# KF01A-D.net
KiCad netlist of a schematic drawn in Altium Designer
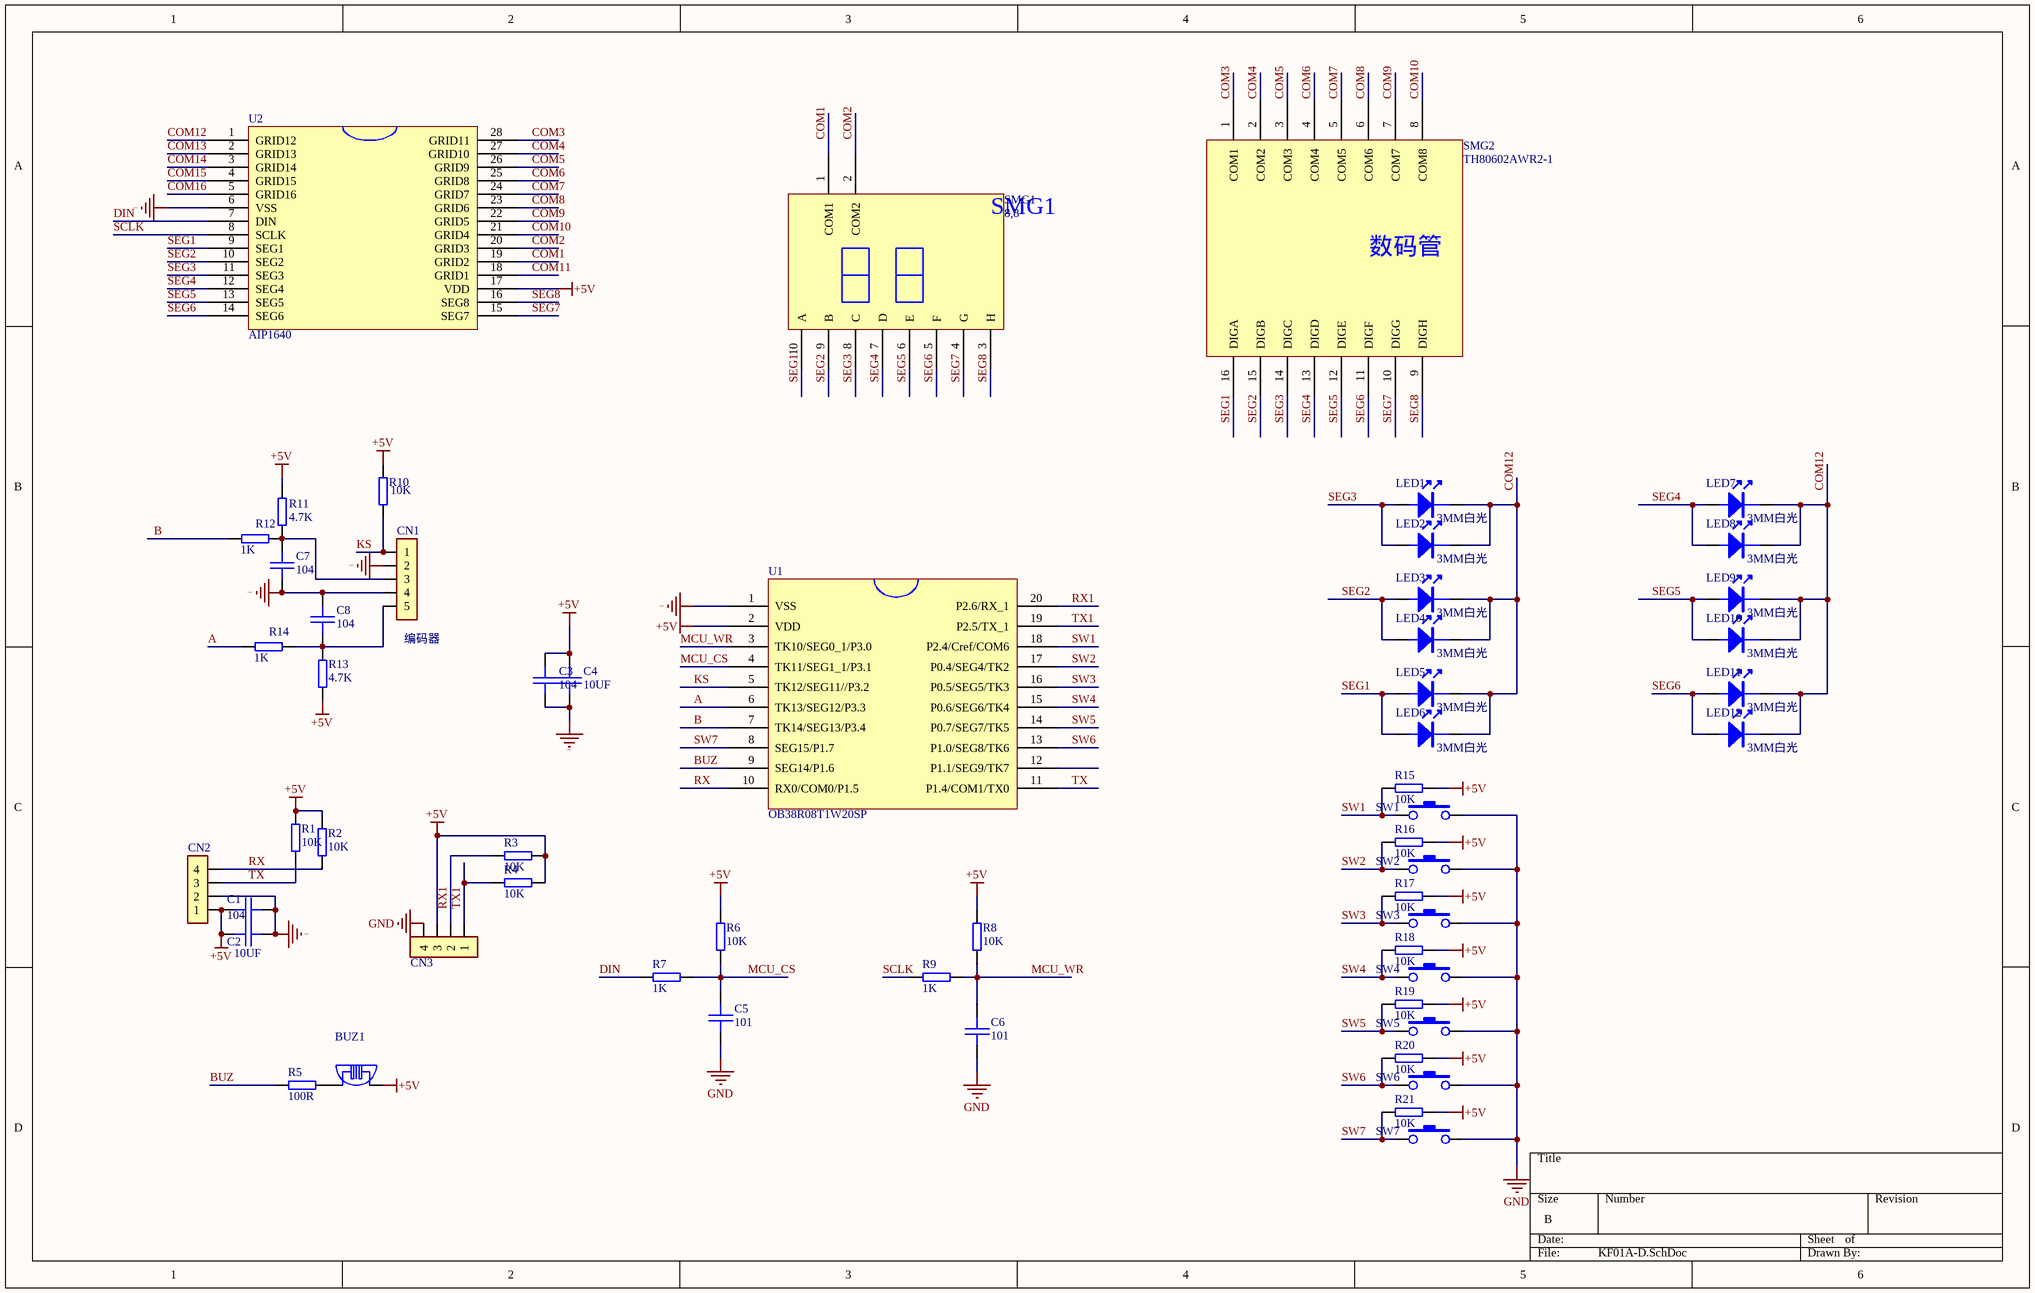
[diagram p0: KF01A-D.SchDoc]

(export (version "E")
  (design (tool "Eeschema 10.0.6"))
  (components
    (comp (ref "BUZ1")
      (value "~")
      (footprint "MD-PCB-201802标准化:BUZ-7.5-15-AI")
      (description "BUZ")
      (libsource (lib "Md-SCH-201802标准化.LIB") (part "BUZ"))
    )
    (comp (ref "C1")
      (value "104")
      (footprint "c0805")
      (description "CAP")
      (libsource (lib "Md-SCH-201802标准化.LIB") (part "C"))
    )
    (comp (ref "C2")
      (value "10UF")
      (footprint "c1206")
      (description "CAP")
      (libsource (lib "Md-SCH-201802标准化.LIB") (part "C"))
    )
    (comp (ref "C3")
      (value "104")
      (footprint "c0805")
      (description "CAP")
      (libsource (lib "Md-SCH-201802标准化.LIB") (part "C"))
    )
    (comp (ref "C4")
      (value "10UF")
      (footprint "c1206")
      (description "CAP")
      (libsource (lib "Md-SCH-201802标准化.LIB") (part "C"))
    )
    (comp (ref "C5")
      (value "101")
      (footprint "c0805")
      (description "CAP")
      (libsource (lib "Md-SCH-201802标准化.LIB") (part "C"))
    )
    (comp (ref "C6")
      (value "101")
      (footprint "c0805")
      (description "CAP")
      (libsource (lib "Md-SCH-201802标准化.LIB") (part "C"))
    )
    (comp (ref "C7")
      (value "104")
      (footprint "c0805")
      (description "CAP")
      (libsource (lib "Md-SCH-201802标准化.LIB") (part "C"))
    )
    (comp (ref "C8")
      (value "104")
      (footprint "c0805")
      (description "CAP")
      (libsource (lib "Md-SCH-201802标准化.LIB") (part "C"))
    )
    (comp (ref "CN1")
      (value "编码器")
      (footprint "抄板封装:编码器")
      (description "CN5")
      (libsource (lib "Md-SCH-201802标准化.LIB") (part "CN5"))
    )
    (comp (ref "CN2")
      (value "~")
      (footprint "CN-2.54-4-X")
      (description "CN4")
      (libsource (lib "Md-SCH-201802标准化.LIB") (part "CN4"))
    )
    (comp (ref "CN3")
      (value "~")
      (footprint "CN-2.54-4-P")
      (description "CN4")
      (libsource (lib "") (part "CN4_1"))
    )
    (comp (ref "LED1")
      (value "3MM白光")
      (footprint "通用库 MD-PCB-20181218:led3")
      (description "LED")
      (libsource (lib "Md-SCH-201802标准化.LIB") (part "DL"))
    )
    (comp (ref "LED2")
      (value "3MM白光")
      (footprint "通用库 MD-PCB-20181218:led3")
      (description "LED")
      (libsource (lib "Md-SCH-201802标准化.LIB") (part "DL"))
    )
    (comp (ref "LED3")
      (value "3MM白光")
      (footprint "通用库 MD-PCB-20181218:led3")
      (description "LED")
      (libsource (lib "Md-SCH-201802标准化.LIB") (part "DL"))
    )
    (comp (ref "LED4")
      (value "3MM白光")
      (footprint "通用库 MD-PCB-20181218:led3")
      (description "LED")
      (libsource (lib "Md-SCH-201802标准化.LIB") (part "DL"))
    )
    (comp (ref "LED5")
      (value "3MM白光")
      (footprint "通用库 MD-PCB-20181218:led3")
      (description "LED")
      (libsource (lib "Md-SCH-201802标准化.LIB") (part "DL"))
    )
    (comp (ref "LED6")
      (value "3MM白光")
      (footprint "通用库 MD-PCB-20181218:led3")
      (description "LED")
      (libsource (lib "Md-SCH-201802标准化.LIB") (part "DL"))
    )
    (comp (ref "LED7")
      (value "3MM白光")
      (footprint "通用库 MD-PCB-20181218:led3")
      (description "LED")
      (libsource (lib "Md-SCH-201802标准化.LIB") (part "DL"))
    )
    (comp (ref "LED8")
      (value "3MM白光")
      (footprint "通用库 MD-PCB-20181218:led3")
      (description "LED")
      (libsource (lib "Md-SCH-201802标准化.LIB") (part "DL"))
    )
    (comp (ref "LED9")
      (value "3MM白光")
      (footprint "通用库 MD-PCB-20181218:led3")
      (description "LED")
      (libsource (lib "Md-SCH-201802标准化.LIB") (part "DL"))
    )
    (comp (ref "LED10")
      (value "3MM白光")
      (footprint "通用库 MD-PCB-20181218:led3")
      (description "LED")
      (libsource (lib "Md-SCH-201802标准化.LIB") (part "DL"))
    )
    (comp (ref "LED11")
      (value "3MM白光")
      (footprint "通用库 MD-PCB-20181218:led3")
      (description "LED")
      (libsource (lib "Md-SCH-201802标准化.LIB") (part "DL"))
    )
    (comp (ref "LED12")
      (value "3MM白光")
      (footprint "通用库 MD-PCB-20181218:led3")
      (description "LED")
      (libsource (lib "Md-SCH-201802标准化.LIB") (part "DL"))
    )
    (comp (ref "R1")
      (value "10K")
      (footprint "R0805")
      (description "RES")
      (libsource (lib "Md-SCH-201802标准化.LIB") (part "R"))
    )
    (comp (ref "R2")
      (value "10K")
      (footprint "R0805")
      (description "RES")
      (libsource (lib "Md-SCH-201802标准化.LIB") (part "R"))
    )
    (comp (ref "R3")
      (value "10K")
      (footprint "R0805")
      (description "RES")
      (libsource (lib "Md-SCH-201802标准化.LIB") (part "R"))
    )
    (comp (ref "R4")
      (value "10K")
      (footprint "R0805")
      (description "RES")
      (libsource (lib "Md-SCH-201802标准化.LIB") (part "R"))
    )
    (comp (ref "R5")
      (value "100R")
      (footprint "R0805")
      (description "RES")
      (libsource (lib "Md-SCH-201802标准化.LIB") (part "R"))
    )
    (comp (ref "R6")
      (value "10K")
      (footprint "R0805")
      (description "RES")
      (libsource (lib "Md-SCH-201802标准化.LIB") (part "R"))
    )
    (comp (ref "R7")
      (value "1K")
      (footprint "R0805")
      (description "RES")
      (libsource (lib "Md-SCH-201802标准化.LIB") (part "R"))
    )
    (comp (ref "R8")
      (value "10K")
      (footprint "R0805")
      (description "RES")
      (libsource (lib "Md-SCH-201802标准化.LIB") (part "R"))
    )
    (comp (ref "R9")
      (value "1K")
      (footprint "R0805")
      (description "RES")
      (libsource (lib "Md-SCH-201802标准化.LIB") (part "R"))
    )
    (comp (ref "R10")
      (value "10K")
      (footprint "R0805")
      (description "RES")
      (libsource (lib "Md-SCH-201802标准化.LIB") (part "R"))
    )
    (comp (ref "R11")
      (value "4.7K")
      (footprint "R0805")
      (description "RES")
      (libsource (lib "Md-SCH-201802标准化.LIB") (part "R"))
    )
    (comp (ref "R12")
      (value "1K")
      (footprint "R0805")
      (description "RES")
      (libsource (lib "Md-SCH-201802标准化.LIB") (part "R"))
    )
    (comp (ref "R13")
      (value "4.7K")
      (footprint "R0805")
      (description "RES")
      (libsource (lib "Md-SCH-201802标准化.LIB") (part "R"))
    )
    (comp (ref "R14")
      (value "1K")
      (footprint "R0805")
      (description "RES")
      (libsource (lib "Md-SCH-201802标准化.LIB") (part "R"))
    )
    (comp (ref "R15")
      (value "10K")
      (footprint "R0805")
      (description "RES")
      (libsource (lib "Md-SCH-201802标准化.LIB") (part "R"))
    )
    (comp (ref "R16")
      (value "10K")
      (footprint "R0805")
      (description "RES")
      (libsource (lib "Md-SCH-201802标准化.LIB") (part "R"))
    )
    (comp (ref "R17")
      (value "10K")
      (footprint "R0805")
      (description "RES")
      (libsource (lib "Md-SCH-201802标准化.LIB") (part "R"))
    )
    (comp (ref "R18")
      (value "10K")
      (footprint "R0805")
      (description "RES")
      (libsource (lib "Md-SCH-201802标准化.LIB") (part "R"))
    )
    (comp (ref "R19")
      (value "10K")
      (footprint "R0805")
      (description "RES")
      (libsource (lib "Md-SCH-201802标准化.LIB") (part "R"))
    )
    (comp (ref "R20")
      (value "10K")
      (footprint "R0805")
      (description "RES")
      (libsource (lib "Md-SCH-201802标准化.LIB") (part "R"))
    )
    (comp (ref "R21")
      (value "10K")
      (footprint "R0805")
      (description "RES")
      (libsource (lib "Md-SCH-201802标准化.LIB") (part "R"))
    )
    (comp (ref "SMG1") (value "8,8") (footprint "TH34251AW1-1") (libsource (lib "CS1621G0") (part "8,8")))
    (comp (ref "SMG2")
      (value "TH80602AWR2-1")
      (footprint "TH80602AWR2-1")
      (libsource (lib "CS1621G0") (part "TH80602AWR2-1"))
    )
    (comp (ref "SW1")
      (value "~")
      (footprint "KEY-4/4")
      (description "KEY")
      (libsource (lib "Md-SCH-201802标准化.LIB") (part "KQ"))
    )
    (comp (ref "SW2")
      (value "~")
      (footprint "KEY-4/4")
      (description "KEY")
      (libsource (lib "Md-SCH-201802标准化.LIB") (part "KQ"))
    )
    (comp (ref "SW3")
      (value "~")
      (footprint "KEY-4/4")
      (description "KEY")
      (libsource (lib "Md-SCH-201802标准化.LIB") (part "KQ"))
    )
    (comp (ref "SW4")
      (value "~")
      (footprint "KEY-4/4")
      (description "KEY")
      (libsource (lib "Md-SCH-201802标准化.LIB") (part "KQ"))
    )
    (comp (ref "SW5")
      (value "~")
      (footprint "KEY-4/4")
      (description "KEY")
      (libsource (lib "Md-SCH-201802标准化.LIB") (part "KQ"))
    )
    (comp (ref "SW6")
      (value "~")
      (footprint "KEY-4/4")
      (description "KEY")
      (libsource (lib "Md-SCH-201802标准化.LIB") (part "KQ"))
    )
    (comp (ref "SW7")
      (value "~")
      (footprint "KEY-4/4")
      (description "KEY")
      (libsource (lib "Md-SCH-201802标准化.LIB") (part "KQ"))
    )
    (comp (ref "U1")
      (value "OB38R08T1W20SP")
      (footprint "通用库 MD-PCB-20181218:SOP20")
      (libsource (lib "Md-SCH-201802标准化.LIB") (part "IC-20"))
    )
    (comp (ref "U2")
      (value "AIP1640")
      (footprint "通用库 MD-PCB-20181218:SOP28")
      (libsource (lib "*") (part "TM1628"))
    )
  )
  (nets
    (net (code "1") (name "+5V") (class "Default")
      (node (ref "BUZ1") (pin "2") (pinfunction "2_2") (pintype "passive"))
      (node (ref "C1") (pin "2") (pinfunction "2_2") (pintype "passive"))
      (node (ref "C2") (pin "2") (pinfunction "2_2") (pintype "passive"))
      (node (ref "C3") (pin "1") (pinfunction "1_1") (pintype "passive"))
      (node (ref "C4") (pin "1") (pinfunction "1_1") (pintype "passive"))
      (node (ref "CN2") (pin "1") (pinfunction "1_1") (pintype "passive"))
      (node (ref "CN3") (pin "3") (pinfunction "3_3") (pintype "passive"))
      (node (ref "R1") (pin "2") (pinfunction "2_2") (pintype "passive"))
      (node (ref "R10") (pin "2") (pinfunction "2_2") (pintype "passive"))
      (node (ref "R11") (pin "1") (pinfunction "1_1") (pintype "passive"))
      (node (ref "R13") (pin "2") (pinfunction "2_2") (pintype "passive"))
      (node (ref "R15") (pin "1") (pinfunction "1_1") (pintype "passive"))
      (node (ref "R16") (pin "1") (pinfunction "1_1") (pintype "passive"))
      (node (ref "R17") (pin "1") (pinfunction "1_1") (pintype "passive"))
      (node (ref "R18") (pin "1") (pinfunction "1_1") (pintype "passive"))
      (node (ref "R19") (pin "1") (pinfunction "1_1") (pintype "passive"))
      (node (ref "R2") (pin "2") (pinfunction "2_2") (pintype "passive"))
      (node (ref "R20") (pin "1") (pinfunction "1_1") (pintype "passive"))
      (node (ref "R21") (pin "1") (pinfunction "1_1") (pintype "passive"))
      (node (ref "R3") (pin "1") (pinfunction "1_1") (pintype "passive"))
      (node (ref "R4") (pin "1") (pinfunction "1_1") (pintype "passive"))
      (node (ref "R6") (pin "2") (pinfunction "2_2") (pintype "passive"))
      (node (ref "R8") (pin "2") (pinfunction "2_2") (pintype "passive"))
      (node (ref "U1") (pin "2") (pinfunction "VDD_2") (pintype "passive"))
      (node (ref "U2") (pin "17") (pinfunction "VDD_17") (pintype "passive"))
    )
    (net (code "2") (name "/A") (class "Default")
      (node (ref "R14") (pin "1") (pinfunction "1_1") (pintype "passive"))
      (node (ref "U1") (pin "6") (pinfunction "TK13/SEG12/P3.3_6") (pintype "passive"))
    )
    (net (code "3") (name "/B") (class "Default")
      (node (ref "R12") (pin "1") (pinfunction "1_1") (pintype "passive"))
      (node (ref "U1") (pin "7") (pinfunction "TK14/SEG13/P3.4_7") (pintype "passive"))
    )
    (net (code "4") (name "/BUZ") (class "Default")
      (node (ref "R5") (pin "2") (pinfunction "2_2") (pintype "passive"))
      (node (ref "U1") (pin "9") (pinfunction "SEG14/P1.6_9") (pintype "passive"))
    )
    (net (code "5") (name "/COM1") (class "Default")
      (node (ref "SMG1") (pin "1") (pinfunction "COM1_1") (pintype "passive"))
      (node (ref "U2") (pin "19") (pinfunction "GRID2_19") (pintype "passive"))
    )
    (net (code "6") (name "/COM2") (class "Default")
      (node (ref "SMG1") (pin "2") (pinfunction "COM2_2") (pintype "passive"))
      (node (ref "U2") (pin "20") (pinfunction "GRID3_20") (pintype "passive"))
    )
    (net (code "7") (name "/COM3") (class "Default")
      (node (ref "SMG2") (pin "1") (pinfunction "COM1_1") (pintype "passive"))
      (node (ref "U2") (pin "28") (pinfunction "GRID11_28") (pintype "passive"))
    )
    (net (code "8") (name "/COM4") (class "Default")
      (node (ref "SMG2") (pin "2") (pinfunction "COM2_2") (pintype "passive"))
      (node (ref "U2") (pin "27") (pinfunction "GRID10_27") (pintype "passive"))
    )
    (net (code "9") (name "/COM5") (class "Default")
      (node (ref "SMG2") (pin "3") (pinfunction "COM3_3") (pintype "passive"))
      (node (ref "U2") (pin "26") (pinfunction "GRID9_26") (pintype "passive"))
    )
    (net (code "10") (name "/COM6") (class "Default")
      (node (ref "SMG2") (pin "4") (pinfunction "COM4_4") (pintype "passive"))
      (node (ref "U2") (pin "25") (pinfunction "GRID8_25") (pintype "passive"))
    )
    (net (code "11") (name "/COM7") (class "Default")
      (node (ref "SMG2") (pin "5") (pinfunction "COM5_5") (pintype "passive"))
      (node (ref "U2") (pin "24") (pinfunction "GRID7_24") (pintype "passive"))
    )
    (net (code "12") (name "/COM8") (class "Default")
      (node (ref "SMG2") (pin "6") (pinfunction "COM6_6") (pintype "passive"))
      (node (ref "U2") (pin "23") (pinfunction "GRID6_23") (pintype "passive"))
    )
    (net (code "13") (name "/COM9") (class "Default")
      (node (ref "SMG2") (pin "7") (pinfunction "COM7_7") (pintype "passive"))
      (node (ref "U2") (pin "22") (pinfunction "GRID5_22") (pintype "passive"))
    )
    (net (code "14") (name "/COM10") (class "Default")
      (node (ref "SMG2") (pin "8") (pinfunction "COM8_8") (pintype "passive"))
      (node (ref "U2") (pin "21") (pinfunction "GRID4_21") (pintype "passive"))
    )
    (net (code "15") (name "/COM11") (class "Default")
      (node (ref "U2") (pin "18") (pinfunction "GRID1_18") (pintype "passive"))
    )
    (net (code "16") (name "/COM12") (class "Default")
      (node (ref "LED1") (pin "K") (pinfunction "K_K") (pintype "passive"))
      (node (ref "LED10") (pin "K") (pinfunction "K_K") (pintype "passive"))
      (node (ref "LED11") (pin "K") (pinfunction "K_K") (pintype "passive"))
      (node (ref "LED12") (pin "K") (pinfunction "K_K") (pintype "passive"))
      (node (ref "LED2") (pin "K") (pinfunction "K_K") (pintype "passive"))
      (node (ref "LED3") (pin "K") (pinfunction "K_K") (pintype "passive"))
      (node (ref "LED4") (pin "K") (pinfunction "K_K") (pintype "passive"))
      (node (ref "LED5") (pin "K") (pinfunction "K_K") (pintype "passive"))
      (node (ref "LED6") (pin "K") (pinfunction "K_K") (pintype "passive"))
      (node (ref "LED7") (pin "K") (pinfunction "K_K") (pintype "passive"))
      (node (ref "LED8") (pin "K") (pinfunction "K_K") (pintype "passive"))
      (node (ref "LED9") (pin "K") (pinfunction "K_K") (pintype "passive"))
      (node (ref "U2") (pin "1") (pinfunction "GRID12_1") (pintype "passive"))
    )
    (net (code "17") (name "/COM13") (class "Default")
      (node (ref "U2") (pin "2") (pinfunction "GRID13_2") (pintype "passive"))
    )
    (net (code "18") (name "/COM14") (class "Default")
      (node (ref "U2") (pin "3") (pinfunction "GRID14_3") (pintype "passive"))
    )
    (net (code "19") (name "/COM15") (class "Default")
      (node (ref "U2") (pin "4") (pinfunction "GRID15_4") (pintype "passive"))
    )
    (net (code "20") (name "/COM16") (class "Default")
      (node (ref "U2") (pin "5") (pinfunction "GRID16_5") (pintype "passive"))
    )
    (net (code "21") (name "/DIN") (class "Default")
      (node (ref "R7") (pin "2") (pinfunction "2_2") (pintype "passive"))
      (node (ref "U2") (pin "7") (pinfunction "DIN_7") (pintype "passive"))
    )
    (net (code "22") (name "/KS") (class "Default")
      (node (ref "CN1") (pin "1") (pinfunction "1_1") (pintype "passive"))
      (node (ref "R10") (pin "1") (pinfunction "1_1") (pintype "passive"))
      (node (ref "U1") (pin "5") (pinfunction "TK12/SEG11//P3.2_5") (pintype "passive"))
    )
    (net (code "23") (name "/MCU_CS") (class "Default")
      (node (ref "C5") (pin "1") (pinfunction "1_1") (pintype "passive"))
      (node (ref "R6") (pin "1") (pinfunction "1_1") (pintype "passive"))
      (node (ref "R7") (pin "1") (pinfunction "1_1") (pintype "passive"))
      (node (ref "U1") (pin "4") (pinfunction "TK11/SEG1_1/P3.1_4") (pintype "passive"))
    )
    (net (code "24") (name "/MCU_WR") (class "Default")
      (node (ref "C6") (pin "1") (pinfunction "1_1") (pintype "passive"))
      (node (ref "R8") (pin "1") (pinfunction "1_1") (pintype "passive"))
      (node (ref "R9") (pin "1") (pinfunction "1_1") (pintype "passive"))
      (node (ref "U1") (pin "3") (pinfunction "TK10/SEG0_1/P3.0_3") (pintype "passive"))
    )
    (net (code "25") (name "/RX") (class "Default")
      (node (ref "CN2") (pin "4") (pinfunction "4_4") (pintype "passive"))
      (node (ref "R2") (pin "1") (pinfunction "1_1") (pintype "passive"))
      (node (ref "U1") (pin "10") (pinfunction "RX0/COM0/P1.5_10") (pintype "passive"))
    )
    (net (code "26") (name "/RX1") (class "Default")
      (node (ref "CN3") (pin "2") (pinfunction "2_2") (pintype "passive"))
      (node (ref "R3") (pin "2") (pinfunction "2_2") (pintype "passive"))
      (node (ref "U1") (pin "20") (pinfunction "P2.6/RX_1_20") (pintype "passive"))
    )
    (net (code "27") (name "/SCLK") (class "Default")
      (node (ref "R9") (pin "2") (pinfunction "2_2") (pintype "passive"))
      (node (ref "U2") (pin "8") (pinfunction "SCLK_8") (pintype "passive"))
    )
    (net (code "28") (name "/SEG1") (class "Default")
      (node (ref "LED5") (pin "A") (pinfunction "A_A") (pintype "passive"))
      (node (ref "LED6") (pin "A") (pinfunction "A_A") (pintype "passive"))
      (node (ref "SMG1") (pin "10") (pinfunction "A_10") (pintype "passive"))
      (node (ref "SMG2") (pin "16") (pinfunction "DIGA_16") (pintype "passive"))
      (node (ref "U2") (pin "9") (pinfunction "SEG1_9") (pintype "passive"))
    )
    (net (code "29") (name "/SEG2") (class "Default")
      (node (ref "LED3") (pin "A") (pinfunction "A_A") (pintype "passive"))
      (node (ref "LED4") (pin "A") (pinfunction "A_A") (pintype "passive"))
      (node (ref "SMG1") (pin "9") (pinfunction "B_9") (pintype "passive"))
      (node (ref "SMG2") (pin "15") (pinfunction "DIGB_15") (pintype "passive"))
      (node (ref "U2") (pin "10") (pinfunction "SEG2_10") (pintype "passive"))
    )
    (net (code "30") (name "/SEG3") (class "Default")
      (node (ref "LED1") (pin "A") (pinfunction "A_A") (pintype "passive"))
      (node (ref "LED2") (pin "A") (pinfunction "A_A") (pintype "passive"))
      (node (ref "SMG1") (pin "8") (pinfunction "C_8") (pintype "passive"))
      (node (ref "SMG2") (pin "14") (pinfunction "DIGC_14") (pintype "passive"))
      (node (ref "U2") (pin "11") (pinfunction "SEG3_11") (pintype "passive"))
    )
    (net (code "31") (name "/SEG4") (class "Default")
      (node (ref "LED7") (pin "A") (pinfunction "A_A") (pintype "passive"))
      (node (ref "LED8") (pin "A") (pinfunction "A_A") (pintype "passive"))
      (node (ref "SMG1") (pin "7") (pinfunction "D_7") (pintype "passive"))
      (node (ref "SMG2") (pin "13") (pinfunction "DIGD_13") (pintype "passive"))
      (node (ref "U2") (pin "12") (pinfunction "SEG4_12") (pintype "passive"))
    )
    (net (code "32") (name "/SEG5") (class "Default")
      (node (ref "LED10") (pin "A") (pinfunction "A_A") (pintype "passive"))
      (node (ref "LED9") (pin "A") (pinfunction "A_A") (pintype "passive"))
      (node (ref "SMG1") (pin "6") (pinfunction "E_6") (pintype "passive"))
      (node (ref "SMG2") (pin "12") (pinfunction "DIGE_12") (pintype "passive"))
      (node (ref "U2") (pin "13") (pinfunction "SEG5_13") (pintype "passive"))
    )
    (net (code "33") (name "/SEG6") (class "Default")
      (node (ref "LED11") (pin "A") (pinfunction "A_A") (pintype "passive"))
      (node (ref "LED12") (pin "A") (pinfunction "A_A") (pintype "passive"))
      (node (ref "SMG1") (pin "5") (pinfunction "F_5") (pintype "passive"))
      (node (ref "SMG2") (pin "11") (pinfunction "DIGF_11") (pintype "passive"))
      (node (ref "U2") (pin "14") (pinfunction "SEG6_14") (pintype "passive"))
    )
    (net (code "34") (name "/SEG7") (class "Default")
      (node (ref "SMG1") (pin "4") (pinfunction "G_4") (pintype "passive"))
      (node (ref "SMG2") (pin "10") (pinfunction "DIGG_10") (pintype "passive"))
      (node (ref "U2") (pin "15") (pinfunction "SEG7_15") (pintype "passive"))
    )
    (net (code "35") (name "/SEG8") (class "Default")
      (node (ref "SMG1") (pin "3") (pinfunction "H_3") (pintype "passive"))
      (node (ref "SMG2") (pin "9") (pinfunction "DIGH_9") (pintype "passive"))
      (node (ref "U2") (pin "16") (pinfunction "SEG8_16") (pintype "passive"))
    )
    (net (code "36") (name "/SW1") (class "Default")
      (node (ref "R15") (pin "2") (pinfunction "2_2") (pintype "passive"))
      (node (ref "SW1") (pin "1") (pinfunction "1_1") (pintype "passive"))
      (node (ref "U1") (pin "18") (pinfunction "P2.4/Cref/COM6_18") (pintype "passive"))
    )
    (net (code "37") (name "/SW2") (class "Default")
      (node (ref "R16") (pin "2") (pinfunction "2_2") (pintype "passive"))
      (node (ref "SW2") (pin "1") (pinfunction "1_1") (pintype "passive"))
      (node (ref "U1") (pin "17") (pinfunction "P0.4/SEG4/TK2_17") (pintype "passive"))
    )
    (net (code "38") (name "/SW3") (class "Default")
      (node (ref "R17") (pin "2") (pinfunction "2_2") (pintype "passive"))
      (node (ref "SW3") (pin "1") (pinfunction "1_1") (pintype "passive"))
      (node (ref "U1") (pin "16") (pinfunction "P0.5/SEG5/TK3_16") (pintype "passive"))
    )
    (net (code "39") (name "/SW4") (class "Default")
      (node (ref "R18") (pin "2") (pinfunction "2_2") (pintype "passive"))
      (node (ref "SW4") (pin "1") (pinfunction "1_1") (pintype "passive"))
      (node (ref "U1") (pin "15") (pinfunction "P0.6/SEG6/TK4_15") (pintype "passive"))
    )
    (net (code "40") (name "/SW5") (class "Default")
      (node (ref "R19") (pin "2") (pinfunction "2_2") (pintype "passive"))
      (node (ref "SW5") (pin "1") (pinfunction "1_1") (pintype "passive"))
      (node (ref "U1") (pin "14") (pinfunction "P0.7/SEG7/TK5_14") (pintype "passive"))
    )
    (net (code "41") (name "/SW6") (class "Default")
      (node (ref "R20") (pin "2") (pinfunction "2_2") (pintype "passive"))
      (node (ref "SW6") (pin "1") (pinfunction "1_1") (pintype "passive"))
      (node (ref "U1") (pin "13") (pinfunction "P1.0/SEG8/TK6_13") (pintype "passive"))
    )
    (net (code "42") (name "/SW7") (class "Default")
      (node (ref "R21") (pin "2") (pinfunction "2_2") (pintype "passive"))
      (node (ref "SW7") (pin "1") (pinfunction "1_1") (pintype "passive"))
      (node (ref "U1") (pin "8") (pinfunction "SEG15/P1.7_8") (pintype "passive"))
    )
    (net (code "43") (name "/TX") (class "Default")
      (node (ref "CN2") (pin "3") (pinfunction "3_3") (pintype "passive"))
      (node (ref "R1") (pin "1") (pinfunction "1_1") (pintype "passive"))
      (node (ref "U1") (pin "11") (pinfunction "P1.4/COM1/TX0_11") (pintype "passive"))
    )
    (net (code "44") (name "/TX1") (class "Default")
      (node (ref "CN3") (pin "1") (pinfunction "1_1") (pintype "passive"))
      (node (ref "R4") (pin "2") (pinfunction "2_2") (pintype "passive"))
      (node (ref "U1") (pin "19") (pinfunction "P2.5/TX_1_19") (pintype "passive"))
    )
    (net (code "45") (name "GND") (class "Default")
      (node (ref "C1") (pin "1") (pinfunction "1_1") (pintype "passive"))
      (node (ref "C2") (pin "1") (pinfunction "1_1") (pintype "passive"))
      (node (ref "C3") (pin "2") (pinfunction "2_2") (pintype "passive"))
      (node (ref "C4") (pin "2") (pinfunction "2_2") (pintype "passive"))
      (node (ref "C5") (pin "2") (pinfunction "2_2") (pintype "passive"))
      (node (ref "C6") (pin "2") (pinfunction "2_2") (pintype "passive"))
      (node (ref "C7") (pin "2") (pinfunction "2_2") (pintype "passive"))
      (node (ref "C8") (pin "1") (pinfunction "1_1") (pintype "passive"))
      (node (ref "CN1") (pin "2") (pinfunction "2_2") (pintype "passive"))
      (node (ref "CN1") (pin "4") (pinfunction "4_4") (pintype "passive"))
      (node (ref "CN2") (pin "2") (pinfunction "2_2") (pintype "passive"))
      (node (ref "CN3") (pin "4") (pinfunction "4_4") (pintype "passive"))
      (node (ref "SW1") (pin "2") (pinfunction "2_2") (pintype "passive"))
      (node (ref "SW2") (pin "2") (pinfunction "2_2") (pintype "passive"))
      (node (ref "SW3") (pin "2") (pinfunction "2_2") (pintype "passive"))
      (node (ref "SW4") (pin "2") (pinfunction "2_2") (pintype "passive"))
      (node (ref "SW5") (pin "2") (pinfunction "2_2") (pintype "passive"))
      (node (ref "SW6") (pin "2") (pinfunction "2_2") (pintype "passive"))
      (node (ref "SW7") (pin "2") (pinfunction "2_2") (pintype "passive"))
      (node (ref "U1") (pin "1") (pinfunction "VSS_1") (pintype "passive"))
      (node (ref "U2") (pin "6") (pinfunction "VSS_6") (pintype "passive"))
    )
    (net (code "46") (name "Net-(BUZ1-Pad1)") (class "Default")
      (node (ref "BUZ1") (pin "1") (pinfunction "1_1") (pintype "passive"))
      (node (ref "R5") (pin "1") (pinfunction "1_1") (pintype "passive"))
    )
    (net (code "47") (name "Net-(C7-Pad1)") (class "Default")
      (node (ref "C7") (pin "1") (pinfunction "1_1") (pintype "passive"))
      (node (ref "CN1") (pin "3") (pinfunction "3_3") (pintype "passive"))
      (node (ref "R11") (pin "2") (pinfunction "2_2") (pintype "passive"))
      (node (ref "R12") (pin "2") (pinfunction "2_2") (pintype "passive"))
    )
    (net (code "48") (name "Net-(C8-Pad2)") (class "Default")
      (node (ref "C8") (pin "2") (pinfunction "2_2") (pintype "passive"))
      (node (ref "CN1") (pin "5") (pinfunction "5_5") (pintype "passive"))
      (node (ref "R13") (pin "1") (pinfunction "1_1") (pintype "passive"))
      (node (ref "R14") (pin "2") (pinfunction "2_2") (pintype "passive"))
    )
    (net (code "49") (name "unconnected-(U1-P1.1{slash}SEG9{slash}TK7-Pad12)") (class "Default")
      (node (ref "U1") (pin "12") (pinfunction "P1.1/SEG9/TK7_12") (pintype "passive"))
    )
  )
)
